# 03-power.net
KiCad netlist of a schematic drawn in Altium Designer
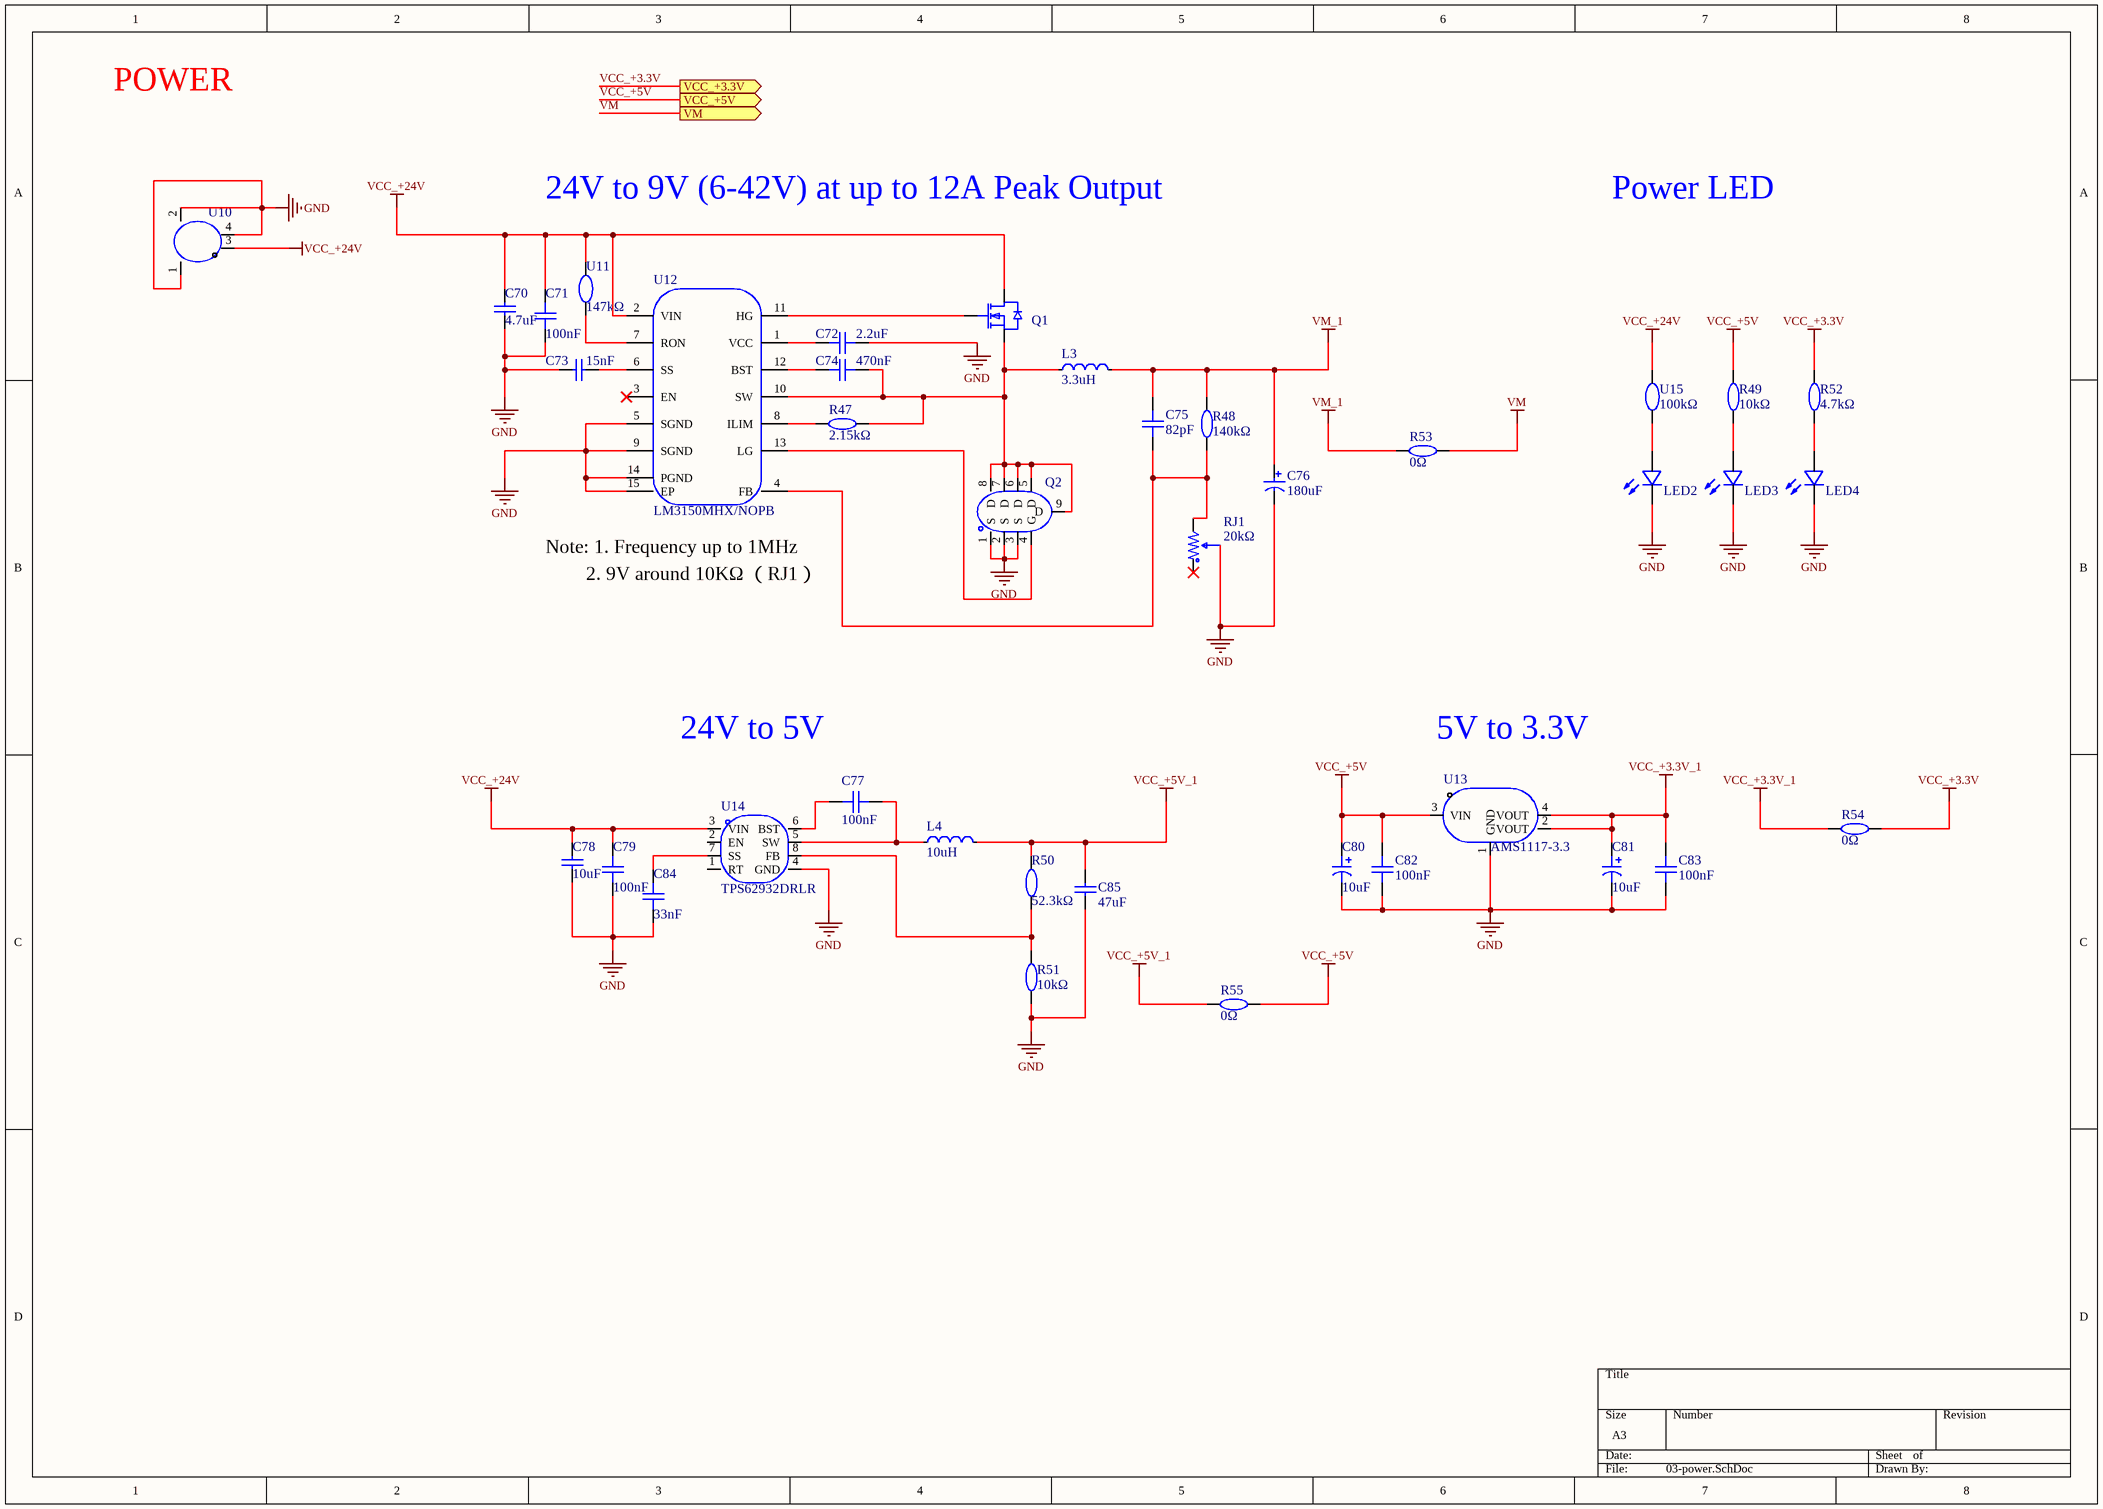
[diagram p0: 03-power.SchDoc]

(export (version "E")
  (design (tool "Eeschema 10.0.6"))
  (components
    (comp (ref "C70")
      (value "4.7uF")
      (footprint "C1206")
      (description "1206电容")
      (fields
        (field (name "MANUFACTURER") "SAMSUNG(三星)")
        (field (name "MANUFACTURER PART") "CL31B475KBHNNNE")
      )
      (libsource (lib "SchLib") (part "C1206_4.7uF"))
    )
    (comp (ref "C71")
      (value "100nF")
      (footprint "C0603")
      (description "0603电容")
      (fields
        (field (name "MANUFACTURER") "SAMSUNG(三星)")
        (field (name "MANUFACTURER PART") "CC0603KRX7R9BB104")
      )
      (libsource (lib "SchLib") (part "C0603_100nF"))
    )
    (comp (ref "C72")
      (value "2.2uF")
      (footprint "C0603")
      (description "0603电容")
      (fields
        (field (name "MANUFACTURER") "SAMSUNG(三星)")
        (field (name "MANUFACTURER PART") "CC0603KRX7R9BB104")
      )
      (libsource (lib "SchLib") (part "C0603_2.2uF"))
    )
    (comp (ref "C73")
      (value "15nF")
      (footprint "C1206")
      (description "1206电容")
      (fields
        (field (name "MANUFACTURER") "Chinocera(华瓷)")
        (field (name "MANUFACTURER PART") "CL31B475KBHNNNE")
      )
      (libsource (lib "SchLib") (part "C1206_15nF"))
    )
    (comp (ref "C74")
      (value "470nF")
      (footprint "C0603")
      (description "0603电容")
      (fields
        (field (name "MANUFACTURER") "SAMSUNG(三星)")
        (field (name "MANUFACTURER PART") "CC0603KRX7R9BB104")
      )
      (libsource (lib "SchLib") (part "C0603_470nF"))
    )
    (comp (ref "C75")
      (value "82pF")
      (footprint "C0805")
      (description "0805电容")
      (fields
        (field (name "MANUFACTURER") "YAGEO(国巨)")
        (field (name "MANUFACTURER PART") "CC0805FRNPO9BN820")
      )
      (libsource (lib "SchLib") (part "C0805_82pF"))
    )
    (comp (ref "C76")
      (value "180uF")
      (footprint "SMD6.3_10_180uF")
      (description "贴片型铝电解电容")
      (fields (field (name "MANUFACTURER") "PANASONIC(松下)") (field (name "MANUFACTURER PART") "16SVPE180M"))
      (libsource (lib "SchLib") (part "SMD6.3_10_180uF"))
    )
    (comp (ref "C77")
      (value "100nF")
      (footprint "C0402_2.2uF")
      (description "0402电容")
      (fields
        (field (name "MANUFACTURER") "muRata(村田)")
        (field (name "MANUFACTURER PART") "GRM155R71H104KE14D")
      )
      (libsource (lib "SchLib") (part "C0402_100nF"))
    )
    (comp (ref "C78")
      (value "10uF")
      (footprint "C1206")
      (description "1206电容")
      (fields
        (field (name "MANUFACTURER") "SAMSUNG(三星)")
        (field (name "MANUFACTURER PART") "CL31B475KBHNNNE")
      )
      (libsource (lib "SchLib") (part "C1206_10uF"))
    )
    (comp (ref "C79")
      (value "100nF")
      (footprint "C0402_2.2uF")
      (description "0402电容")
      (fields
        (field (name "MANUFACTURER") "muRata(村田)")
        (field (name "MANUFACTURER PART") "GRM155R71H104KE14D")
      )
      (libsource (lib "SchLib") (part "C0402_100nF"))
    )
    (comp (ref "C80")
      (value "10uF")
      (footprint "SMD5_5.4_10uF")
      (description "贴片型铝电解电容")
      (fields (field (name "MANUFACTURER") "KNSCHA(科尼盛)") (field (name "MANUFACTURER PART") "RST10UF50V016"))
      (libsource (lib "SchLib") (part "SMD5_5.4_10uF"))
    )
    (comp (ref "C81")
      (value "10uF")
      (footprint "SMD5_5.4_10uF")
      (description "贴片型铝电解电容")
      (fields (field (name "MANUFACTURER") "KNSCHA(科尼盛)") (field (name "MANUFACTURER PART") "RST10UF50V016"))
      (libsource (lib "SchLib") (part "SMD5_5.4_10uF"))
    )
    (comp (ref "C82")
      (value "100nF")
      (footprint "C0603")
      (description "0603电容")
      (fields
        (field (name "MANUFACTURER") "SAMSUNG(三星)")
        (field (name "MANUFACTURER PART") "CC0603KRX7R9BB104")
      )
      (libsource (lib "SchLib") (part "C0603_100nF"))
    )
    (comp (ref "C83")
      (value "100nF")
      (footprint "C0603")
      (description "0603电容")
      (fields
        (field (name "MANUFACTURER") "SAMSUNG(三星)")
        (field (name "MANUFACTURER PART") "CC0603KRX7R9BB104")
      )
      (libsource (lib "SchLib") (part "C0603_100nF"))
    )
    (comp (ref "C84")
      (value "33nF")
      (footprint "C0402_2.2uF")
      (description "0402电容")
      (fields
        (field (name "MANUFACTURER") "FOJAN(富捷)")
        (field (name "MANUFACTURER PART") "GRM155R71H104KE14D")
      )
      (libsource (lib "SchLib") (part "C0402_33nF"))
    )
    (comp (ref "C85")
      (value "47uF")
      (footprint "C1206")
      (description "1206电容")
      (fields (field (name "MANUFACTURER") "HRE(芯声)") (field (name "MANUFACTURER PART") "CL31B475KBHNNNE"))
      (libsource (lib "SchLib") (part "C1206_47uF"))
    )
    (comp (ref "L3")
      (value "3.3uH")
      (footprint "L1360")
      (description "电感值 3.3uH   精度 ±20%   额定电流 16A   饱和电流(Isat) 22A   直流电阻(DCR) 6mΩ   类型 一体成型电感")
      (fields (field (name "MANUFACTURER") "SXN(顺翔诺)") (field (name "MANUFACTURER PART") "SMMS1360-3R3M"))
      (libsource (lib "SchLib") (part "L1360_3.3uH"))
    )
    (comp (ref "L4")
      (value "10uH")
      (footprint "L1110_10uH")
      (description "功率电感")
      (fields (field (name "MANUFACTURER") "YJYCOIN(益嘉源)") (field (name "MANUFACTURER PART") "YSPI1050-100M"))
      (libsource (lib "SchLib") (part "L1110_10uH"))
    )
    (comp (ref "LED2")
      (value "MHT192UGCT")
      (footprint "LED")
      (description "发光二极管 绿色")
      (fields (field (name "MANUFACTURER") "MEIHUA(美华)"))
      (libsource (lib "SchLib") (part "LED"))
    )
    (comp (ref "LED3")
      (value "MHT192UGCT")
      (footprint "LED")
      (description "发光二极管 绿色")
      (fields (field (name "MANUFACTURER") "MEIHUA(美华)"))
      (libsource (lib "SchLib") (part "LED"))
    )
    (comp (ref "LED4")
      (value "MHT192UGCT")
      (footprint "LED")
      (description "发光二极管 绿色")
      (fields (field (name "MANUFACTURER") "MEIHUA(美华)"))
      (libsource (lib "SchLib") (part "LED"))
    )
    (comp (ref "Q1")
      (value "IRLR8726TRPBF")
      (footprint "NMOS")
      (description "1个N沟道 耐压:30V 电流:86A")
      (fields (field (name "MANUFACTURER") "Infineon(英飞凌)"))
      (libsource (lib "SchLib") (part "NMOS"))
    )
    (comp (ref "Q2")
      (value "CSD18533Q5A")
      (footprint "CSD18533Q5A")
      (description "NMOS 漏源电压(Vdss) 60V   连续漏极电流(Id) 17A；100A   功率(Pd) 3.2W；116W   导通电阻(RDS(on)@Vgs,Id) 5.9mΩ@10V,18A")
      (fields (field (name "MANUFACTURER") "TI(德州仪器)"))
      (libsource (lib "SchLib") (part "CSD18533Q5A"))
    )
    (comp (ref "R47")
      (value "2.15kΩ")
      (footprint "R0603")
      (description "0603电阻")
      (fields (field (name "MANUFACTURER") "YAGEO(国巨)") (field (name "MANUFACTURER PART") "0603WAF2001T5E"))
      (libsource (lib "SchLib") (part "R0603_2.15KΩ"))
    )
    (comp (ref "R48")
      (value "140kΩ")
      (footprint "R0805")
      (description "0805电阻")
      (fields
        (field (name "MANUFACTURER") "UNI-ROYAL(厚声)")
        (field (name "MANUFACTURER PART") "0805W8F1403T5E")
      )
      (libsource (lib "SchLib") (part "R0805_140KΩ"))
    )
    (comp (ref "R49")
      (value "10kΩ")
      (footprint "R0603_10KΩ")
      (description "0603电阻")
      (fields
        (field (name "MANUFACTURER") "UNI-ROYAL(厚声)")
        (field (name "MANUFACTURER PART") "0603WAF1002T5E")
      )
      (libsource (lib "SchLib") (part "R0603_10KΩ"))
    )
    (comp (ref "R50")
      (value "52.3kΩ")
      (footprint "R0603_10KΩ")
      (description "0603电阻")
      (fields (field (name "MANUFACTURER") "FOJAN(富捷)") (field (name "MANUFACTURER PART") "0603WAF1002T5E"))
      (libsource (lib "SchLib") (part "R0603_52.3KΩ"))
    )
    (comp (ref "R51")
      (value "10kΩ")
      (footprint "R0603_10KΩ")
      (description "0603电阻")
      (fields
        (field (name "MANUFACTURER") "UNI-ROYAL(厚声)")
        (field (name "MANUFACTURER PART") "0603WAF1002T5E")
      )
      (libsource (lib "SchLib") (part "R0603_10KΩ"))
    )
    (comp (ref "R52")
      (value "4.7kΩ")
      (footprint "R0603_10KΩ")
      (description "0603电阻")
      (fields
        (field (name "MANUFACTURER") "UNI-ROYAL(厚声)")
        (field (name "MANUFACTURER PART") "0603WAF1002T5E")
      )
      (libsource (lib "SchLib") (part "R0603_4.7KΩ"))
    )
    (comp (ref "R53")
      (value "0Ω")
      (footprint "R0603")
      (description "阻值 0Ω   精度 ±1%   功率 100mW   最大工作电压 75V   工作温度范围 -55℃~+155℃")
      (fields
        (field (name "MANUFACTURER") "UNI-ROYAL(厚声)")
        (field (name "MANUFACTURER PART") "0603WAF0000T5E")
      )
      (libsource (lib "SchLib") (part "R0603_0Ω"))
    )
    (comp (ref "R54")
      (value "0Ω")
      (footprint "R0603")
      (description "阻值 0Ω   精度 ±1%   功率 100mW   最大工作电压 75V   工作温度范围 -55℃~+155℃")
      (fields
        (field (name "MANUFACTURER") "UNI-ROYAL(厚声)")
        (field (name "MANUFACTURER PART") "0603WAF0000T5E")
      )
      (libsource (lib "SchLib") (part "R0603_0Ω"))
    )
    (comp (ref "R55")
      (value "0Ω")
      (footprint "R0603")
      (description "阻值 0Ω   精度 ±1%   功率 100mW   最大工作电压 75V   工作温度范围 -55℃~+155℃")
      (fields
        (field (name "MANUFACTURER") "UNI-ROYAL(厚声)")
        (field (name "MANUFACTURER PART") "0603WAF0000T5E")
      )
      (libsource (lib "SchLib") (part "R0603_0Ω"))
    )
    (comp (ref "RJ1")
      (value "20kΩ")
      (footprint "R20k_KT")
      (description "可调电阻，20K")
      (fields (field (name "MANUFACTURER") "BOURNS") (field (name "MANUFACTURER PART") "TC33X-2-203E"))
      (libsource (lib "SchLib") (part "R20k_KT"))
    )
    (comp (ref "U10")
      (value "XT60PW-F")
      (footprint "XT60PW-F")
      (description "卧式插头")
      (fields (field (name "MANUFACTURER") "AMASS(艾迈斯)"))
      (libsource (lib "SchLib") (part "XT60PW-F"))
    )
    (comp (ref "U11")
      (value "147kΩ")
      (footprint "R0603")
      (description "0603电阻")
      (fields (field (name "MANUFACTURER") "FOJAN(富捷)") (field (name "MANUFACTURER PART") "FRC0603F1473TS"))
      (libsource (lib "SchLib") (part "R0603_147KΩ"))
    )
    (comp (ref "U12")
      (value "LM3150MHX/NOPB")
      (footprint "LM3150MHX/NOPB")
      (description "DC-DC电源芯片   功能类型 降压型   输入电压 6V~42V   输出电流 12A   开关频率 1MHz")
      (fields (field (name "MANUFACTURER") "TI(德州仪器)"))
      (libsource (lib "SchLib") (part "LM3150MHX/NOPB"))
    )
    (comp (ref "U13")
      (value "AMS1117-3.3")
      (footprint "AMS1117-3.3")
      (description "5V-3.3V")
      (fields (field (name "MANUFACTURER") "AMS"))
      (libsource (lib "SchLib") (part "AMS1117-3.3"))
    )
    (comp (ref "U14")
      (value "TPS62932DRLR")
      (footprint "TPS62932DRLR")
      (description "DCDC BUCK")
      (fields (field (name "MANUFACTURER") "TI(德州仪器)"))
      (libsource (lib "SchLib") (part "TPS62932DRLR"))
    )
    (comp (ref "U15")
      (value "100kΩ")
      (footprint "R0603")
      (description "0603电阻")
      (fields (field (name "MANUFACTURER") "FOJAN(富捷)") (field (name "MANUFACTURER PART") "FRC0603F1473TS"))
      (libsource (lib "SchLib") (part "R0603_100KΩ"))
    )
  )
  (nets
    (net (code "1") (name "GND") (class "Default")
      (node (ref "C70") (pin "1") (pinfunction "1_1") (pintype "passive"))
      (node (ref "C71") (pin "1") (pinfunction "1_1") (pintype "passive"))
      (node (ref "C72") (pin "2") (pinfunction "2_2") (pintype "passive"))
      (node (ref "C73") (pin "1") (pinfunction "1_1") (pintype "passive"))
      (node (ref "C76") (pin "2") (pinfunction "2_2") (pintype "passive"))
      (node (ref "C78") (pin "1") (pinfunction "1_1") (pintype "passive"))
      (node (ref "C79") (pin "1") (pinfunction "1_1") (pintype "passive"))
      (node (ref "C80") (pin "2") (pinfunction "2_2") (pintype "passive"))
      (node (ref "C81") (pin "2") (pinfunction "2_2") (pintype "passive"))
      (node (ref "C82") (pin "2") (pinfunction "2_2") (pintype "passive"))
      (node (ref "C83") (pin "2") (pinfunction "2_2") (pintype "passive"))
      (node (ref "C84") (pin "1") (pinfunction "1_1") (pintype "passive"))
      (node (ref "C85") (pin "1") (pinfunction "1_1") (pintype "passive"))
      (node (ref "LED2") (pin "1") (pinfunction "-_1") (pintype "passive"))
      (node (ref "LED3") (pin "1") (pinfunction "-_1") (pintype "passive"))
      (node (ref "LED4") (pin "1") (pinfunction "-_1") (pintype "passive"))
      (node (ref "Q2") (pin "1") (pinfunction "S_1") (pintype "passive"))
      (node (ref "Q2") (pin "2") (pinfunction "S_2") (pintype "passive"))
      (node (ref "Q2") (pin "3") (pinfunction "S_3") (pintype "passive"))
      (node (ref "R51") (pin "1") (pinfunction "1_1") (pintype "passive"))
      (node (ref "RJ1") (pin "2") (pinfunction "2_2") (pintype "passive"))
      (node (ref "U10") (pin "1") (pinfunction "1_1") (pintype "passive"))
      (node (ref "U10") (pin "2") (pinfunction "2_2") (pintype "passive"))
      (node (ref "U10") (pin "4") (pinfunction "4_4") (pintype "passive"))
      (node (ref "U12") (pin "14") (pinfunction "PGND_14") (pintype "passive"))
      (node (ref "U12") (pin "15") (pinfunction "EP_15") (pintype "passive"))
      (node (ref "U12") (pin "5") (pinfunction "SGND_5") (pintype "passive"))
      (node (ref "U12") (pin "9") (pinfunction "SGND_9") (pintype "passive"))
      (node (ref "U13") (pin "1") (pinfunction "GND_1") (pintype "passive"))
      (node (ref "U14") (pin "4") (pinfunction "GND_4") (pintype "passive"))
    )
    (net (code "2") (name "Net-(LED2-+)") (class "Default")
      (node (ref "LED2") (pin "2") (pinfunction "+_2") (pintype "passive"))
      (node (ref "U15") (pin "1") (pinfunction "1_1") (pintype "passive"))
    )
    (net (code "3") (name "Net-(LED3-+)") (class "Default")
      (node (ref "LED3") (pin "2") (pinfunction "+_2") (pintype "passive"))
      (node (ref "R49") (pin "1") (pinfunction "1_1") (pintype "passive"))
    )
    (net (code "4") (name "Net-(LED4-+)") (class "Default")
      (node (ref "LED4") (pin "2") (pinfunction "+_2") (pintype "passive"))
      (node (ref "R52") (pin "1") (pinfunction "1_1") (pintype "passive"))
    )
    (net (code "5") (name "Net-(Q1-G)") (class "Default")
      (node (ref "Q1") (pin "1") (pinfunction "G_1") (pintype "passive"))
      (node (ref "U12") (pin "11") (pinfunction "HG_11") (pintype "passive"))
    )
    (net (code "6") (name "Net-(Q1-S)") (class "Default")
      (node (ref "C74") (pin "2") (pinfunction "2_2") (pintype "passive"))
      (node (ref "L3") (pin "1") (pinfunction "1_1") (pintype "passive"))
      (node (ref "Q1") (pin "3") (pinfunction "S_3") (pintype "passive"))
      (node (ref "Q2") (pin "5") (pinfunction "D_5") (pintype "passive"))
      (node (ref "Q2") (pin "6") (pinfunction "D_6") (pintype "passive"))
      (node (ref "Q2") (pin "7") (pinfunction "D_7") (pintype "passive"))
      (node (ref "Q2") (pin "8") (pinfunction "D_8") (pintype "passive"))
      (node (ref "Q2") (pin "9") (pinfunction "D_9") (pintype "passive"))
      (node (ref "R47") (pin "2") (pinfunction "2_2") (pintype "passive"))
      (node (ref "U12") (pin "10") (pinfunction "SW_10") (pintype "passive"))
    )
    (net (code "7") (name "Net-(Q2-G)") (class "Default")
      (node (ref "Q2") (pin "4") (pinfunction "G_4") (pintype "passive"))
      (node (ref "U12") (pin "13") (pinfunction "LG_13") (pintype "passive"))
    )
    (net (code "8") (name "Net-(U12-BST)") (class "Default")
      (node (ref "C74") (pin "1") (pinfunction "1_1") (pintype "passive"))
      (node (ref "U12") (pin "12") (pinfunction "BST_12") (pintype "passive"))
    )
    (net (code "9") (name "Net-(U12-FB)") (class "Default")
      (node (ref "C75") (pin "1") (pinfunction "1_1") (pintype "passive"))
      (node (ref "R48") (pin "1") (pinfunction "1_1") (pintype "passive"))
      (node (ref "RJ1") (pin "3") (pinfunction "3_3") (pintype "passive"))
      (node (ref "U12") (pin "4") (pinfunction "FB_4") (pintype "passive"))
    )
    (net (code "10") (name "Net-(U12-ILIM)") (class "Default")
      (node (ref "R47") (pin "1") (pinfunction "1_1") (pintype "passive"))
      (node (ref "U12") (pin "8") (pinfunction "ILIM_8") (pintype "passive"))
    )
    (net (code "11") (name "Net-(U12-RON)") (class "Default")
      (node (ref "U11") (pin "1") (pinfunction "1_1") (pintype "passive"))
      (node (ref "U12") (pin "7") (pinfunction "RON_7") (pintype "passive"))
    )
    (net (code "12") (name "Net-(U12-SS)") (class "Default")
      (node (ref "C73") (pin "2") (pinfunction "2_2") (pintype "passive"))
      (node (ref "U12") (pin "6") (pinfunction "SS_6") (pintype "passive"))
    )
    (net (code "13") (name "Net-(U12-VCC)") (class "Default")
      (node (ref "C72") (pin "1") (pinfunction "1_1") (pintype "passive"))
      (node (ref "U12") (pin "1") (pinfunction "VCC_1") (pintype "passive"))
    )
    (net (code "14") (name "Net-(U14-BST)") (class "Default")
      (node (ref "C77") (pin "1") (pinfunction "1_1") (pintype "passive"))
      (node (ref "U14") (pin "6") (pinfunction "BST_6") (pintype "passive"))
    )
    (net (code "15") (name "Net-(U14-FB)") (class "Default")
      (node (ref "R50") (pin "1") (pinfunction "1_1") (pintype "passive"))
      (node (ref "R51") (pin "2") (pinfunction "2_2") (pintype "passive"))
      (node (ref "U14") (pin "8") (pinfunction "FB_8") (pintype "passive"))
    )
    (net (code "16") (name "Net-(U14-SS)") (class "Default")
      (node (ref "C84") (pin "2") (pinfunction "2_2") (pintype "passive"))
      (node (ref "U14") (pin "7") (pinfunction "SS_7") (pintype "passive"))
    )
    (net (code "17") (name "Net-(U14-SW)") (class "Default")
      (node (ref "C77") (pin "2") (pinfunction "2_2") (pintype "passive"))
      (node (ref "L4") (pin "1") (pinfunction "1_1") (pintype "passive"))
      (node (ref "U14") (pin "5") (pinfunction "SW_5") (pintype "passive"))
    )
    (net (code "18") (name "VCC_+3.3V") (class "Default")
      (node (ref "R52") (pin "2") (pinfunction "2_2") (pintype "passive"))
      (node (ref "R54") (pin "2") (pinfunction "2_2") (pintype "passive"))
    )
    (net (code "19") (name "VCC_+3.3V_1") (class "Default")
      (node (ref "C81") (pin "1") (pinfunction "1_1") (pintype "passive"))
      (node (ref "C83") (pin "1") (pinfunction "1_1") (pintype "passive"))
      (node (ref "R54") (pin "1") (pinfunction "1_1") (pintype "passive"))
      (node (ref "U13") (pin "2") (pinfunction "VOUT_2") (pintype "passive"))
      (node (ref "U13") (pin "4") (pinfunction "VOUT_4") (pintype "passive"))
    )
    (net (code "20") (name "VCC_+5V") (class "Default")
      (node (ref "C80") (pin "1") (pinfunction "1_1") (pintype "passive"))
      (node (ref "C82") (pin "1") (pinfunction "1_1") (pintype "passive"))
      (node (ref "R49") (pin "2") (pinfunction "2_2") (pintype "passive"))
      (node (ref "R55") (pin "2") (pinfunction "2_2") (pintype "passive"))
      (node (ref "U13") (pin "3") (pinfunction "VIN_3") (pintype "passive"))
    )
    (net (code "21") (name "VCC_+5V_1") (class "Default")
      (node (ref "C85") (pin "2") (pinfunction "2_2") (pintype "passive"))
      (node (ref "L4") (pin "2") (pinfunction "2_2") (pintype "passive"))
      (node (ref "R50") (pin "2") (pinfunction "2_2") (pintype "passive"))
      (node (ref "R55") (pin "1") (pinfunction "1_1") (pintype "passive"))
    )
    (net (code "22") (name "VCC_+24V") (class "Default")
      (node (ref "C70") (pin "2") (pinfunction "2_2") (pintype "passive"))
      (node (ref "C71") (pin "2") (pinfunction "2_2") (pintype "passive"))
      (node (ref "C78") (pin "2") (pinfunction "2_2") (pintype "passive"))
      (node (ref "C79") (pin "2") (pinfunction "2_2") (pintype "passive"))
      (node (ref "Q1") (pin "2") (pinfunction "D_2") (pintype "passive"))
      (node (ref "U10") (pin "3") (pinfunction "3_3") (pintype "passive"))
      (node (ref "U11") (pin "2") (pinfunction "2_2") (pintype "passive"))
      (node (ref "U12") (pin "2") (pinfunction "VIN_2") (pintype "passive"))
      (node (ref "U14") (pin "3") (pinfunction "VIN_3") (pintype "passive"))
      (node (ref "U15") (pin "2") (pinfunction "2_2") (pintype "passive"))
    )
    (net (code "23") (name "VM") (class "Default")
      (node (ref "R53") (pin "2") (pinfunction "2_2") (pintype "passive"))
    )
    (net (code "24") (name "VM_1") (class "Default")
      (node (ref "C75") (pin "2") (pinfunction "2_2") (pintype "passive"))
      (node (ref "C76") (pin "1") (pinfunction "1_1") (pintype "passive"))
      (node (ref "L3") (pin "2") (pinfunction "2_2") (pintype "passive"))
      (node (ref "R48") (pin "2") (pinfunction "2_2") (pintype "passive"))
      (node (ref "R53") (pin "1") (pinfunction "1_1") (pintype "passive"))
    )
    (net (code "25") (name "unconnected-(RJ1-Pad1)") (class "Default")
      (node (ref "RJ1") (pin "1") (pinfunction "1_1") (pintype "passive+no_connect"))
    )
    (net (code "26") (name "unconnected-(U12-EN-Pad3)") (class "Default")
      (node (ref "U12") (pin "3") (pinfunction "EN_3") (pintype "passive+no_connect"))
    )
    (net (code "27") (name "unconnected-(U14-EN-Pad2)") (class "Default")
      (node (ref "U14") (pin "2") (pinfunction "EN_2") (pintype "passive"))
    )
    (net (code "28") (name "unconnected-(U14-RT-Pad1)") (class "Default")
      (node (ref "U14") (pin "1") (pinfunction "RT_1") (pintype "passive"))
    )
  )
)
